# ir_camera.net
KiCad netlist of a schematic drawn in EAGLE
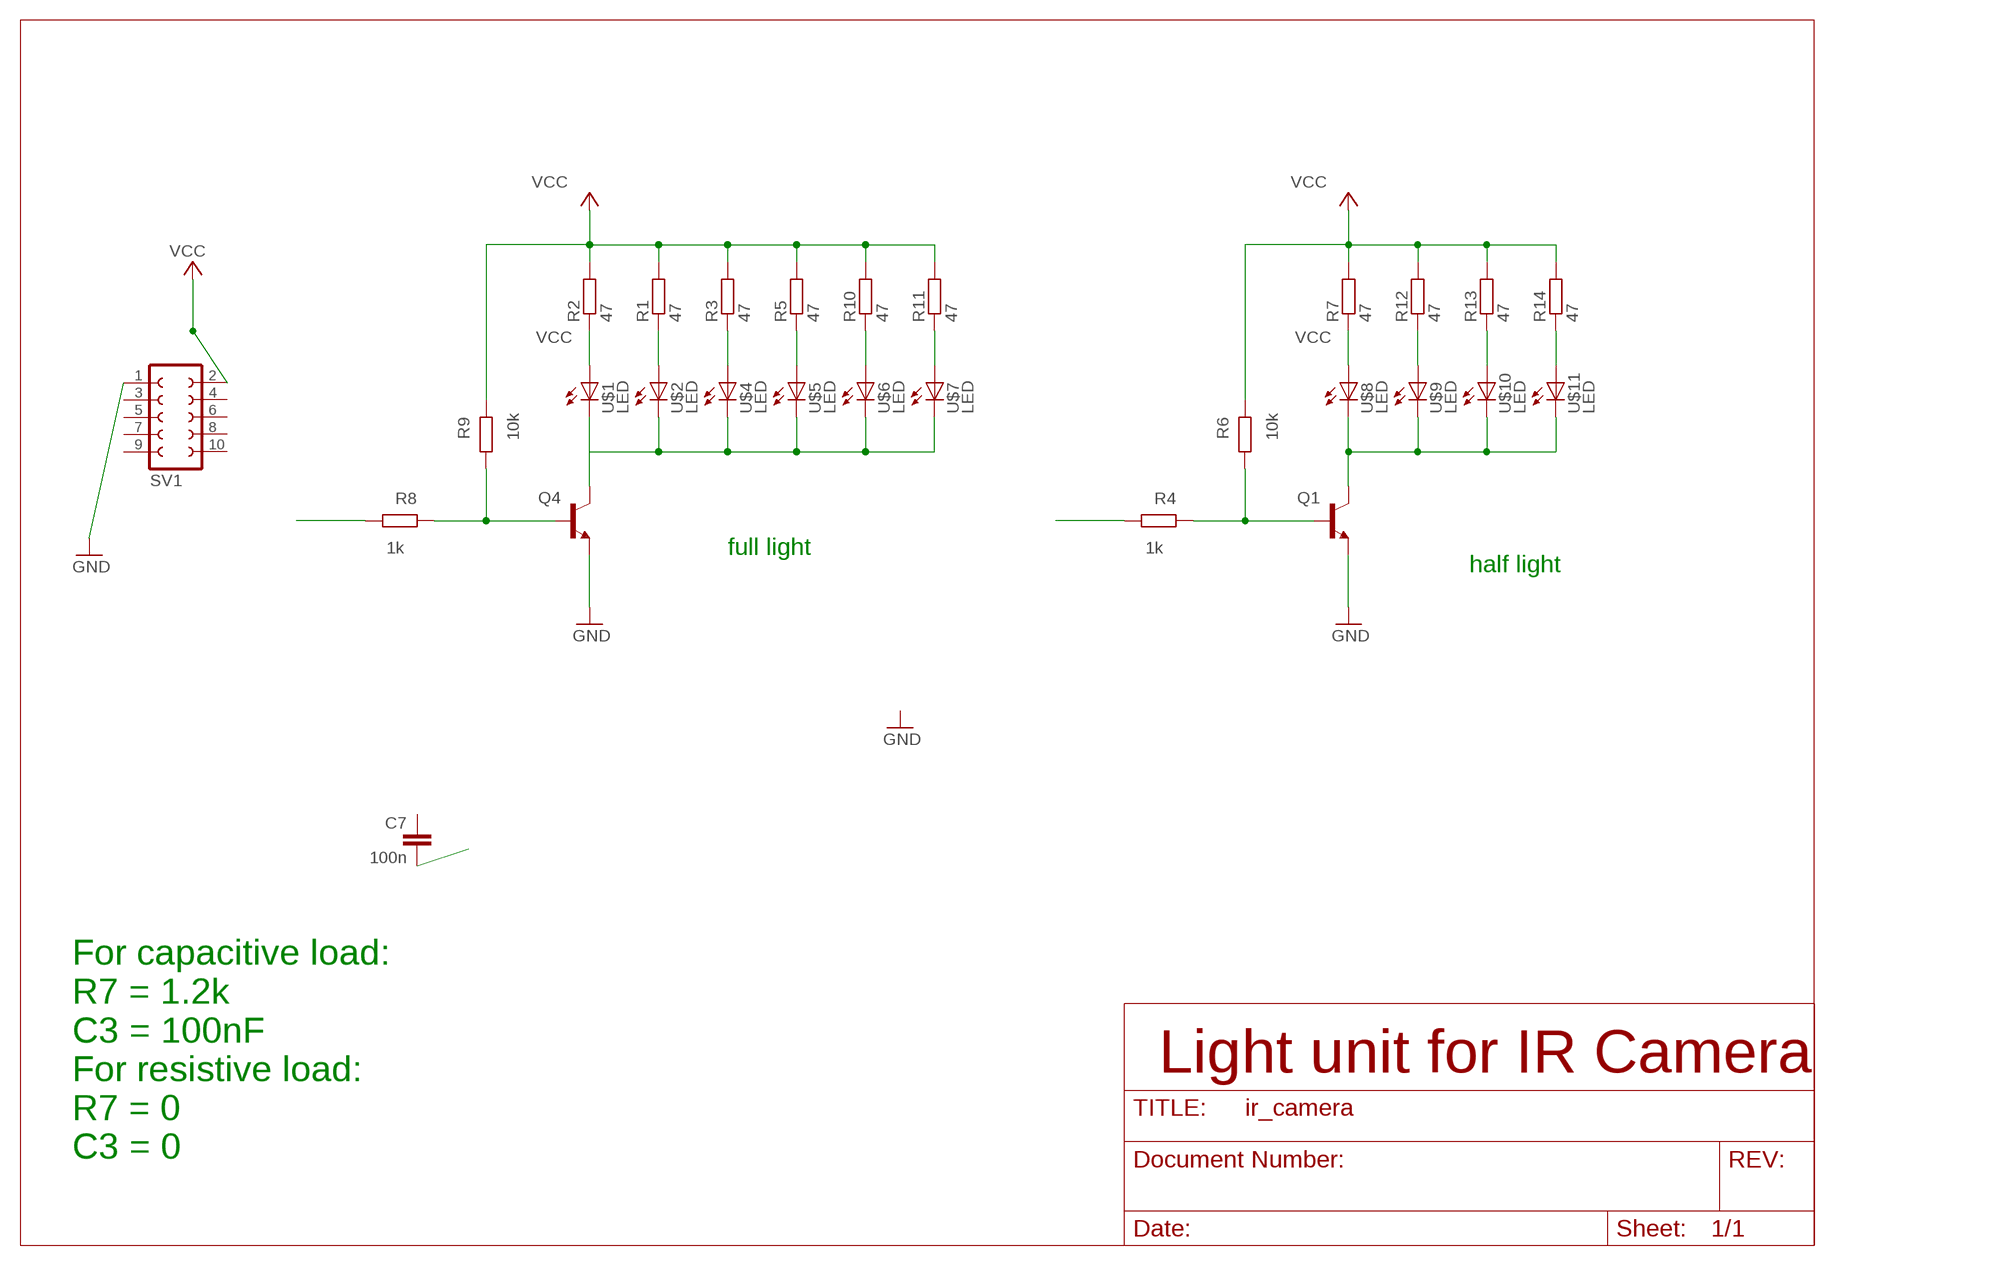
[diagram p0: schematic, sheet 1]

(export (version "E")
  (design (tool "Eeschema 10.0.6"))
  (components
    (comp (ref "C7")
      (value "100n")
      (footprint "eagle-import:C050-024X044")
      (libsource (lib "eagle-import") (part "C-55MM"))
    )
    (comp (ref "Q1")
      (value "BC548")
      (footprint "eagle-import:TO92-EBC")
      (libsource (lib "eagle-import") (part "BC548"))
    )
    (comp (ref "Q4")
      (value "BC548")
      (footprint "eagle-import:TO92-EBC")
      (libsource (lib "eagle-import") (part "BC548"))
    )
    (comp (ref "R1")
      (value "47")
      (footprint "eagle-import:R_0207_2V")
      (libsource (lib "eagle-import") (part "R-EU_0207/2V"))
    )
    (comp (ref "R2")
      (value "47")
      (footprint "eagle-import:R_0207_2V")
      (libsource (lib "eagle-import") (part "R-EU_0207/2V"))
    )
    (comp (ref "R3")
      (value "47")
      (footprint "eagle-import:R_0207_2V")
      (libsource (lib "eagle-import") (part "R-EU_0207/2V"))
    )
    (comp (ref "R4")
      (value "1k")
      (footprint "eagle-import:R_0207_2V")
      (libsource (lib "eagle-import") (part "R-EU_0207/2V"))
    )
    (comp (ref "R5")
      (value "47")
      (footprint "eagle-import:R_0207_2V")
      (libsource (lib "eagle-import") (part "R-EU_0207/2V"))
    )
    (comp (ref "R6")
      (value "10k")
      (footprint "eagle-import:R_0207_2V")
      (libsource (lib "eagle-import") (part "R-EU_0207/2V"))
    )
    (comp (ref "R7")
      (value "47")
      (footprint "eagle-import:R_0207_2V")
      (libsource (lib "eagle-import") (part "R-EU_0207/2V"))
    )
    (comp (ref "R8")
      (value "1k")
      (footprint "eagle-import:R_0207_2V")
      (libsource (lib "eagle-import") (part "R-EU_0207/2V"))
    )
    (comp (ref "R9")
      (value "10k")
      (footprint "eagle-import:R_0207_2V")
      (libsource (lib "eagle-import") (part "R-EU_0207/2V"))
    )
    (comp (ref "R10")
      (value "47")
      (footprint "eagle-import:R_0207_2V")
      (libsource (lib "eagle-import") (part "R-EU_0207/2V"))
    )
    (comp (ref "R11")
      (value "47")
      (footprint "eagle-import:R_0207_2V")
      (libsource (lib "eagle-import") (part "R-EU_0207/2V"))
    )
    (comp (ref "R12")
      (value "47")
      (footprint "eagle-import:R_0207_2V")
      (libsource (lib "eagle-import") (part "R-EU_0207/2V"))
    )
    (comp (ref "R13")
      (value "47")
      (footprint "eagle-import:R_0207_2V")
      (libsource (lib "eagle-import") (part "R-EU_0207/2V"))
    )
    (comp (ref "R14")
      (value "47")
      (footprint "eagle-import:R_0207_2V")
      (libsource (lib "eagle-import") (part "R-EU_0207/2V"))
    )
    (comp (ref "SV1")
      (value "FE05-2")
      (footprint "eagle-import:FE05-2")
      (libsource (lib "eagle-import") (part "FE05-2"))
    )
    (comp (ref "U$1")
      (value "LED")
      (footprint "eagle-import:LED_LD260")
      (libsource (lib "eagle-import") (part "LED"))
    )
    (comp (ref "U$2")
      (value "LED")
      (footprint "eagle-import:LED_LD260")
      (libsource (lib "eagle-import") (part "LED"))
    )
    (comp (ref "U$4")
      (value "LED")
      (footprint "eagle-import:LED_LD260")
      (libsource (lib "eagle-import") (part "LED"))
    )
    (comp (ref "U$5")
      (value "LED")
      (footprint "eagle-import:LED_LD260")
      (libsource (lib "eagle-import") (part "LED"))
    )
    (comp (ref "U$6")
      (value "LED")
      (footprint "eagle-import:LED_LD260")
      (libsource (lib "eagle-import") (part "LED"))
    )
    (comp (ref "U$7")
      (value "LED")
      (footprint "eagle-import:LED_LD260")
      (libsource (lib "eagle-import") (part "LED"))
    )
    (comp (ref "U$8")
      (value "LED")
      (footprint "eagle-import:LED_LD260")
      (libsource (lib "eagle-import") (part "LED"))
    )
    (comp (ref "U$9")
      (value "LED")
      (footprint "eagle-import:LED_LD260")
      (libsource (lib "eagle-import") (part "LED"))
    )
    (comp (ref "U$10")
      (value "LED")
      (footprint "eagle-import:LED_LD260")
      (libsource (lib "eagle-import") (part "LED"))
    )
    (comp (ref "U$11")
      (value "LED")
      (footprint "eagle-import:LED_LD260")
      (libsource (lib "eagle-import") (part "LED"))
    )
  )
  (nets
    (net (code "1") (name "GND") (class "Default")
      (node (ref "Q1") (pin "E") (pinfunction "E_E") (pintype "passive"))
      (node (ref "Q4") (pin "E") (pinfunction "E_E") (pintype "passive"))
      (node (ref "SV1") (pin "1") (pinfunction "1_1") (pintype "passive"))
    )
    (net (code "2") (name "Net-(Q1-PadB)") (class "Default")
      (node (ref "Q1") (pin "B") (pinfunction "B_B") (pintype "passive"))
      (node (ref "R4") (pin "1") (pinfunction "1_1") (pintype "passive"))
      (node (ref "R6") (pin "1") (pinfunction "1_1") (pintype "passive"))
    )
    (net (code "3") (name "Net-(Q4-PadB)") (class "Default")
      (node (ref "Q4") (pin "B") (pinfunction "B_B") (pintype "passive"))
      (node (ref "R8") (pin "1") (pinfunction "1_1") (pintype "passive"))
      (node (ref "R9") (pin "1") (pinfunction "1_1") (pintype "passive"))
    )
    (net (code "4") (name "Net-(R1-Pad1)") (class "Default")
      (node (ref "R1") (pin "1") (pinfunction "1_1") (pintype "passive"))
      (node (ref "U$2") (pin "A") (pinfunction "A_A") (pintype "passive"))
    )
    (net (code "5") (name "Net-(R2-Pad1)") (class "Default")
      (node (ref "R2") (pin "1") (pinfunction "1_1") (pintype "passive"))
      (node (ref "U$1") (pin "A") (pinfunction "A_A") (pintype "passive"))
    )
    (net (code "6") (name "Net-(R3-Pad1)") (class "Default")
      (node (ref "R3") (pin "1") (pinfunction "1_1") (pintype "passive"))
      (node (ref "U$4") (pin "A") (pinfunction "A_A") (pintype "passive"))
    )
    (net (code "7") (name "Net-(R5-Pad1)") (class "Default")
      (node (ref "R5") (pin "1") (pinfunction "1_1") (pintype "passive"))
      (node (ref "U$5") (pin "A") (pinfunction "A_A") (pintype "passive"))
    )
    (net (code "8") (name "Net-(R7-Pad1)") (class "Default")
      (node (ref "R7") (pin "1") (pinfunction "1_1") (pintype "passive"))
      (node (ref "U$8") (pin "A") (pinfunction "A_A") (pintype "passive"))
    )
    (net (code "9") (name "Net-(R10-Pad1)") (class "Default")
      (node (ref "R10") (pin "1") (pinfunction "1_1") (pintype "passive"))
      (node (ref "U$6") (pin "A") (pinfunction "A_A") (pintype "passive"))
    )
    (net (code "10") (name "Net-(R11-Pad1)") (class "Default")
      (node (ref "R11") (pin "1") (pinfunction "1_1") (pintype "passive"))
      (node (ref "U$7") (pin "A") (pinfunction "A_A") (pintype "passive"))
    )
    (net (code "11") (name "Net-(R12-Pad1)") (class "Default")
      (node (ref "R12") (pin "1") (pinfunction "1_1") (pintype "passive"))
      (node (ref "U$9") (pin "A") (pinfunction "A_A") (pintype "passive"))
    )
    (net (code "12") (name "Net-(R13-Pad1)") (class "Default")
      (node (ref "R13") (pin "1") (pinfunction "1_1") (pintype "passive"))
      (node (ref "U$10") (pin "A") (pinfunction "A_A") (pintype "passive"))
    )
    (net (code "13") (name "Net-(R14-Pad1)") (class "Default")
      (node (ref "R14") (pin "1") (pinfunction "1_1") (pintype "passive"))
      (node (ref "U$11") (pin "A") (pinfunction "A_A") (pintype "passive"))
    )
    (net (code "14") (name "Net-(U$1-C)") (class "Default")
      (node (ref "Q4") (pin "C") (pinfunction "C_C") (pintype "passive"))
      (node (ref "U$1") (pin "K") (pinfunction "C_K") (pintype "passive"))
      (node (ref "U$2") (pin "K") (pinfunction "C_K") (pintype "passive"))
      (node (ref "U$4") (pin "K") (pinfunction "C_K") (pintype "passive"))
      (node (ref "U$5") (pin "K") (pinfunction "C_K") (pintype "passive"))
      (node (ref "U$6") (pin "K") (pinfunction "C_K") (pintype "passive"))
      (node (ref "U$7") (pin "K") (pinfunction "C_K") (pintype "passive"))
    )
    (net (code "15") (name "Net-(U$10-C)") (class "Default")
      (node (ref "Q1") (pin "C") (pinfunction "C_C") (pintype "passive"))
      (node (ref "U$10") (pin "K") (pinfunction "C_K") (pintype "passive"))
      (node (ref "U$11") (pin "K") (pinfunction "C_K") (pintype "passive"))
      (node (ref "U$8") (pin "K") (pinfunction "C_K") (pintype "passive"))
      (node (ref "U$9") (pin "K") (pinfunction "C_K") (pintype "passive"))
    )
    (net (code "16") (name "VCC") (class "Default")
      (node (ref "R1") (pin "2") (pinfunction "2_2") (pintype "passive"))
      (node (ref "R10") (pin "2") (pinfunction "2_2") (pintype "passive"))
      (node (ref "R11") (pin "2") (pinfunction "2_2") (pintype "passive"))
      (node (ref "R12") (pin "2") (pinfunction "2_2") (pintype "passive"))
      (node (ref "R13") (pin "2") (pinfunction "2_2") (pintype "passive"))
      (node (ref "R14") (pin "2") (pinfunction "2_2") (pintype "passive"))
      (node (ref "R2") (pin "2") (pinfunction "2_2") (pintype "passive"))
      (node (ref "R3") (pin "2") (pinfunction "2_2") (pintype "passive"))
      (node (ref "R5") (pin "2") (pinfunction "2_2") (pintype "passive"))
      (node (ref "R6") (pin "2") (pinfunction "2_2") (pintype "passive"))
      (node (ref "R7") (pin "2") (pinfunction "2_2") (pintype "passive"))
      (node (ref "R9") (pin "2") (pinfunction "2_2") (pintype "passive"))
      (node (ref "SV1") (pin "2") (pinfunction "2_2") (pintype "passive"))
    )
    (net (code "17") (name "unconnected-(C7-Pad1)") (class "Default")
      (node (ref "C7") (pin "1") (pinfunction "1_1") (pintype "passive"))
    )
    (net (code "18") (name "unconnected-(C7-Pad2)") (class "Default")
      (node (ref "C7") (pin "2") (pinfunction "2_2") (pintype "passive"))
    )
    (net (code "19") (name "unconnected-(R4-Pad2)") (class "Default")
      (node (ref "R4") (pin "2") (pinfunction "2_2") (pintype "passive"))
    )
    (net (code "20") (name "unconnected-(R8-Pad2)") (class "Default")
      (node (ref "R8") (pin "2") (pinfunction "2_2") (pintype "passive"))
    )
    (net (code "21") (name "unconnected-(SV1-Pad3)") (class "Default")
      (node (ref "SV1") (pin "3") (pinfunction "3_3") (pintype "passive"))
    )
    (net (code "22") (name "unconnected-(SV1-Pad4)") (class "Default")
      (node (ref "SV1") (pin "4") (pinfunction "4_4") (pintype "passive"))
    )
    (net (code "23") (name "unconnected-(SV1-Pad5)") (class "Default")
      (node (ref "SV1") (pin "5") (pinfunction "5_5") (pintype "passive"))
    )
    (net (code "24") (name "unconnected-(SV1-Pad6)") (class "Default")
      (node (ref "SV1") (pin "6") (pinfunction "6_6") (pintype "passive"))
    )
    (net (code "25") (name "unconnected-(SV1-Pad7)") (class "Default")
      (node (ref "SV1") (pin "7") (pinfunction "7_7") (pintype "passive"))
    )
    (net (code "26") (name "unconnected-(SV1-Pad8)") (class "Default")
      (node (ref "SV1") (pin "8") (pinfunction "8_8") (pintype "passive"))
    )
    (net (code "27") (name "unconnected-(SV1-Pad9)") (class "Default")
      (node (ref "SV1") (pin "9") (pinfunction "9_9") (pintype "passive"))
    )
    (net (code "28") (name "unconnected-(SV1-Pad10)") (class "Default")
      (node (ref "SV1") (pin "10") (pinfunction "10_10") (pintype "passive"))
    )
  )
)
